# isd_sound_primary.net
KiCad netlist of a schematic drawn in EAGLE
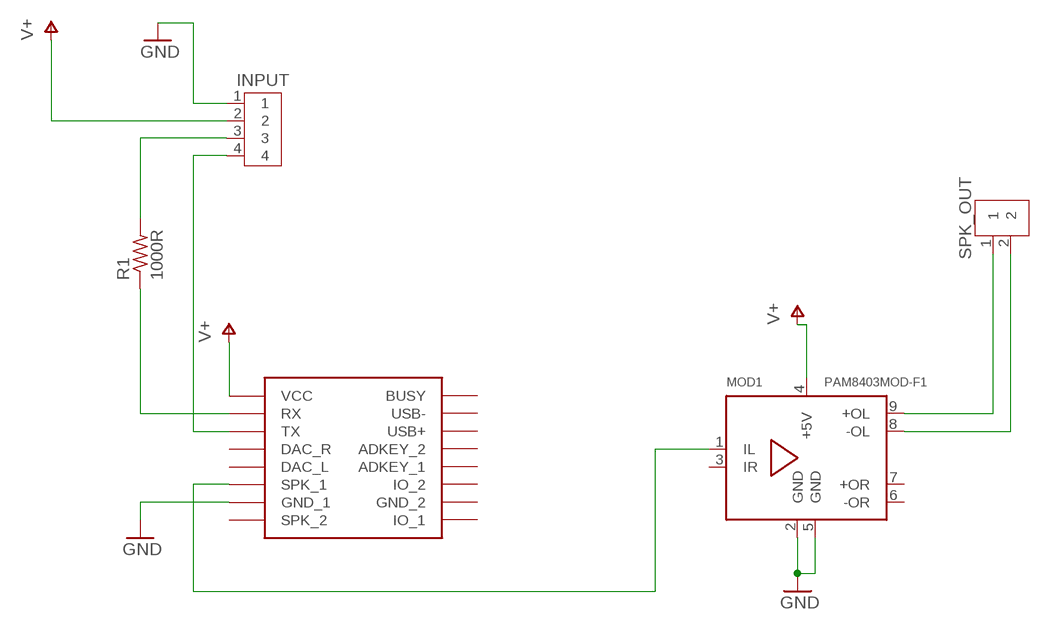
[diagram p0: schematic, sheet 1]

(export (version "E")
  (design (tool "Eeschema 10.0.6"))
  (components
    (comp (ref "INPUT")
      (value "B4B-XH-A")
      (footprint "eagle-import:B4B-XH-A")
      (fields (field (name "MANUFACTURER") "JST (XH connector)"))
      (libsource (lib "eagle-import") (part "B4B-XH-A"))
    )
    (comp (ref "MOD1")
      (value "PAM8403MOD-F1")
      (footprint "eagle-import:PAM8403MOD1")
      (libsource (lib "eagle-import") (part "PAM8403MOD-F1"))
    )
    (comp (ref "R1")
      (value "1000R")
      (footprint "eagle-import:0204V")
      (libsource (lib "eagle-import") (part "R-US_0204/2V"))
    )
    (comp (ref "SPK_OUT")
      (value "B2B-XH-A")
      (footprint "eagle-import:B2B-XH-A")
      (fields (field (name "MANUFACTURER") "JST (XH CONNECTOR)"))
      (libsource (lib "eagle-import") (part "B2B-XH-A"))
    )
    (comp (ref "U$1")
      (value "DFPLAYER")
      (footprint "eagle-import:DFPLAYER")
      (libsource (lib "eagle-import") (part "DFPLAYER"))
    )
  )
  (nets
    (net (code "1") (name "GND") (class "Default")
      (node (ref "INPUT") (pin "1") (pinfunction "1_1") (pintype "bidirectional"))
      (node (ref "MOD1") (pin "2") (pinfunction "GND_2") (pintype "power_in"))
      (node (ref "MOD1") (pin "5") (pinfunction "GND_5") (pintype "power_in"))
      (node (ref "U$1") (pin "GND_1") (pinfunction "GND_1_GND_1") (pintype "bidirectional"))
    )
    (net (code "2") (name "Net-(INPUT-Pad3)") (class "Default")
      (node (ref "INPUT") (pin "3") (pinfunction "3_3") (pintype "bidirectional"))
      (node (ref "R1") (pin "2") (pinfunction "2_2") (pintype "passive"))
    )
    (net (code "3") (name "Net-(INPUT-Pad4)") (class "Default")
      (node (ref "INPUT") (pin "4") (pinfunction "4_4") (pintype "bidirectional"))
      (node (ref "U$1") (pin "TX") (pinfunction "TX_TX") (pintype "bidirectional"))
    )
    (net (code "4") (name "Net-(MOD1-+OL)") (class "Default")
      (node (ref "MOD1") (pin "9") (pinfunction "+OL_9") (pintype "passive"))
      (node (ref "SPK_OUT") (pin "1") (pinfunction "1_1") (pintype "bidirectional"))
    )
    (net (code "5") (name "Net-(MOD1--OL)") (class "Default")
      (node (ref "MOD1") (pin "8") (pinfunction "-OL_8") (pintype "passive"))
      (node (ref "SPK_OUT") (pin "2") (pinfunction "2_2") (pintype "bidirectional"))
    )
    (net (code "6") (name "Net-(MOD1-IL)") (class "Default")
      (node (ref "MOD1") (pin "1") (pinfunction "IL_1") (pintype "passive"))
      (node (ref "U$1") (pin "SPK1") (pinfunction "SPK_1_SPK1") (pintype "bidirectional"))
    )
    (net (code "7") (name "Net-(R1-Pad1)") (class "Default")
      (node (ref "R1") (pin "1") (pinfunction "1_1") (pintype "passive"))
      (node (ref "U$1") (pin "RX") (pinfunction "RX_RX") (pintype "bidirectional"))
    )
    (net (code "8") (name "V+") (class "Default")
      (node (ref "INPUT") (pin "2") (pinfunction "2_2") (pintype "bidirectional"))
      (node (ref "MOD1") (pin "4") (pinfunction "+5V_4") (pintype "power_in"))
      (node (ref "U$1") (pin "VCC") (pinfunction "VCC_VCC") (pintype "bidirectional"))
    )
    (net (code "9") (name "unconnected-(MOD1-+OR-Pad7)") (class "Default")
      (node (ref "MOD1") (pin "7") (pinfunction "+OR_7") (pintype "passive"))
    )
    (net (code "10") (name "unconnected-(MOD1--OR-Pad6)") (class "Default")
      (node (ref "MOD1") (pin "6") (pinfunction "-OR_6") (pintype "passive"))
    )
    (net (code "11") (name "unconnected-(MOD1-IR-Pad3)") (class "Default")
      (node (ref "MOD1") (pin "3") (pinfunction "IR_3") (pintype "passive"))
    )
    (net (code "12") (name "unconnected-(U$1-ADKEY_1-PadADKEY1)") (class "Default")
      (node (ref "U$1") (pin "ADKEY1") (pinfunction "ADKEY_1_ADKEY1") (pintype "bidirectional"))
    )
    (net (code "13") (name "unconnected-(U$1-ADKEY_2-PadADKEY2)") (class "Default")
      (node (ref "U$1") (pin "ADKEY2") (pinfunction "ADKEY_2_ADKEY2") (pintype "bidirectional"))
    )
    (net (code "14") (name "unconnected-(U$1-IO_1-PadIO1)") (class "Default")
      (node (ref "U$1") (pin "IO1") (pinfunction "IO_1_IO1") (pintype "bidirectional"))
    )
    (net (code "15") (name "unconnected-(U$1-IO_2-PadIO2)") (class "Default")
      (node (ref "U$1") (pin "IO2") (pinfunction "IO_2_IO2") (pintype "bidirectional"))
    )
    (net (code "16") (name "unconnected-(U$1-PadBUSY)") (class "Default")
      (node (ref "U$1") (pin "BUSY") (pinfunction "BUSY_BUSY") (pintype "bidirectional"))
    )
    (net (code "17") (name "unconnected-(U$1-PadDAC_L)") (class "Default")
      (node (ref "U$1") (pin "DAC_L") (pinfunction "DAC_L_DAC_L") (pintype "bidirectional"))
    )
    (net (code "18") (name "unconnected-(U$1-PadDAC_R)") (class "Default")
      (node (ref "U$1") (pin "DAC_R") (pinfunction "DAC_R_DAC_R") (pintype "bidirectional"))
    )
    (net (code "19") (name "unconnected-(U$1-PadGND_2)") (class "Default")
      (node (ref "U$1") (pin "GND_2") (pinfunction "GND_2_GND_2") (pintype "bidirectional"))
    )
    (net (code "20") (name "unconnected-(U$1-PadUSB+)") (class "Default")
      (node (ref "U$1") (pin "USB+") (pinfunction "USB+_USB+") (pintype "bidirectional"))
    )
    (net (code "21") (name "unconnected-(U$1-PadUSB-)") (class "Default")
      (node (ref "U$1") (pin "USB-") (pinfunction "USB-_USB-") (pintype "bidirectional"))
    )
    (net (code "22") (name "unconnected-(U$1-SPK_2-PadSPK2)") (class "Default")
      (node (ref "U$1") (pin "SPK2") (pinfunction "SPK_2_SPK2") (pintype "bidirectional"))
    )
  )
)
